# sensors.net
KiCad netlist of a schematic drawn in Altium Designer
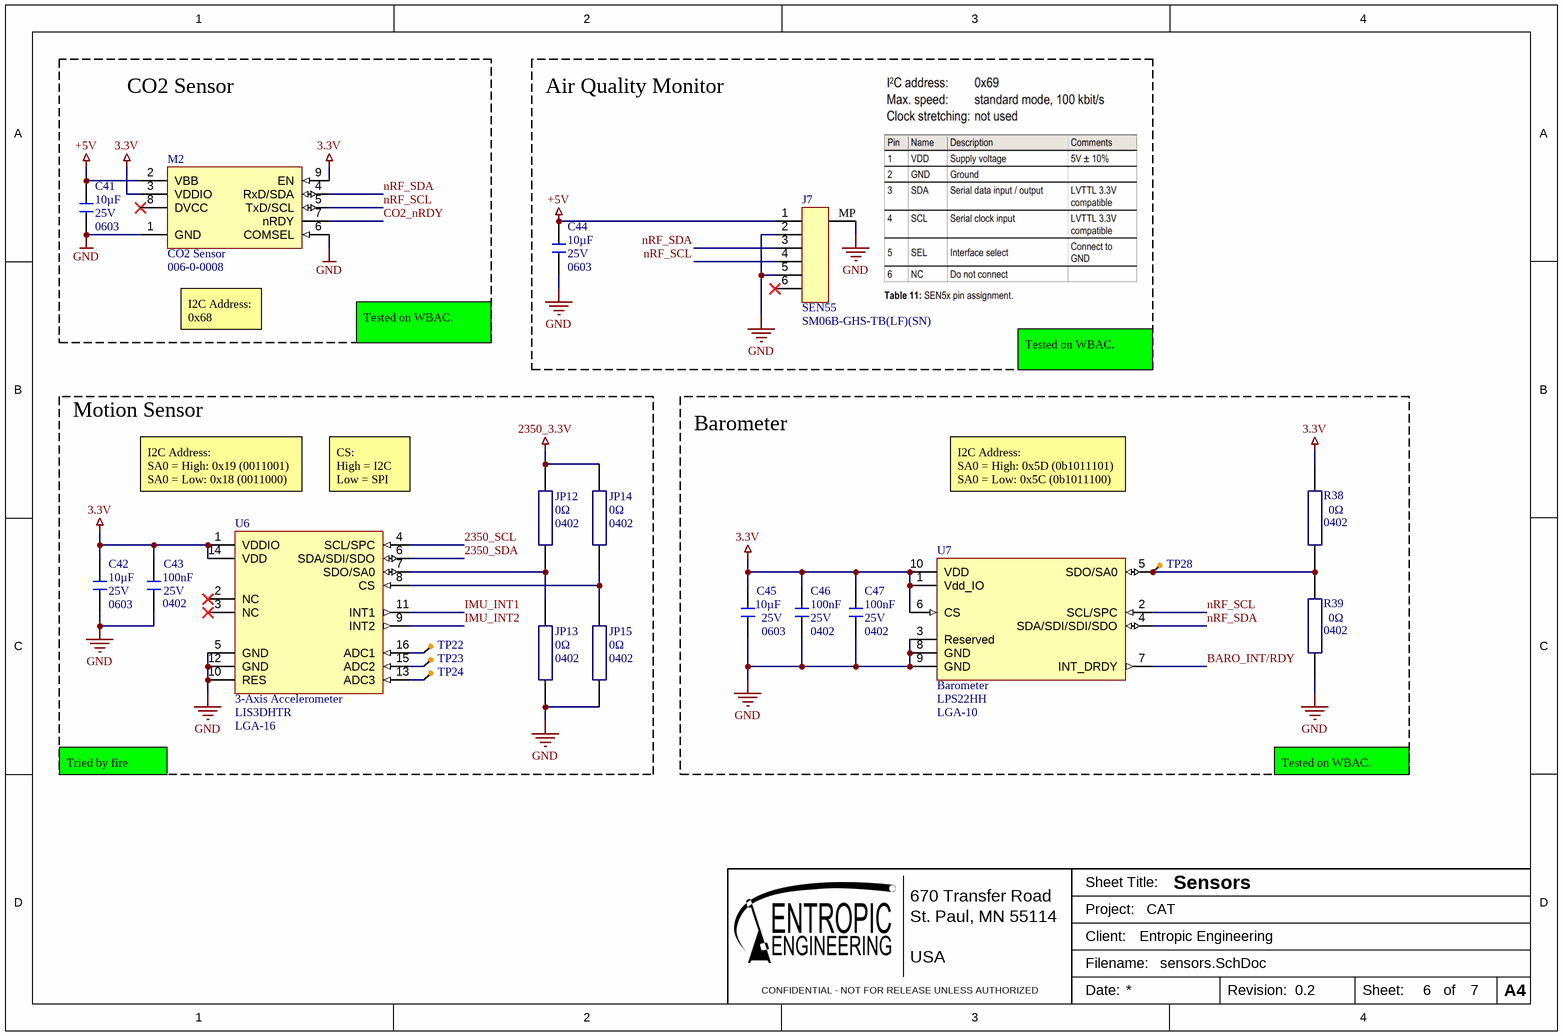
[diagram p0: sensors.SchDoc]

(export (version "E")
  (design (tool "Eeschema 10.0.6"))
  (components
    (comp (ref "C41")
      (value "10µF")
      (footprint "0603_capacitor")
      (description "10 µF, 25 V, X5R, 0603 Chip capacitor")
      (fields
        (field (name "MANUFACTURER") "Samsung")
        (field (name "CASE/PACKAGE") "0603")
        (field (name "TOLERANCE") "20%")
        (field (name "VOLTAGE RATING") "25V")
      )
      (libsource (lib "cat") (part "CL10A106MA8NRNC"))
    )
    (comp (ref "C42")
      (value "10µF")
      (footprint "0603_capacitor")
      (description "10 µF, 25 V, X5R, 0603 Chip capacitor")
      (fields
        (field (name "MANUFACTURER") "Samsung")
        (field (name "CASE/PACKAGE") "0603")
        (field (name "TOLERANCE") "20%")
        (field (name "VOLTAGE RATING") "25V")
      )
      (libsource (lib "cat") (part "CL10A106MA8NRNC"))
    )
    (comp (ref "C43")
      (value "GRM155R71E104KE14D")
      (footprint "0402_capacitor")
      (description "100 nF, 25 V, X7R, 0402 Chip capacitor")
      (fields
        (field (name "MANUFACTURER") "Murata")
        (field (name "TOLERANCE") "10%")
        (field (name "CASE CODE (IMPERIAL)") "0402")
        (field (name "VOLTAGE") "25V")
        (field (name "CAPACITANCE") "100nF")
      )
      (libsource (lib "cat") (part "GRM155R71E104KE14D"))
    )
    (comp (ref "C44")
      (value "10µF")
      (footprint "0603_capacitor")
      (description "10 µF, 25 V, X5R, 0603 Chip capacitor")
      (fields
        (field (name "MANUFACTURER") "Samsung")
        (field (name "CASE/PACKAGE") "0603")
        (field (name "TOLERANCE") "20%")
        (field (name "VOLTAGE RATING") "25V")
      )
      (libsource (lib "cat") (part "CL10A106MA8NRNC"))
    )
    (comp (ref "C45")
      (value "10µF")
      (footprint "0603_capacitor")
      (description "10 µF, 25 V, X5R, 0603 Chip capacitor")
      (fields
        (field (name "MANUFACTURER") "Samsung")
        (field (name "MANUFACTURER PART NUMBER") "CL10A106MA8NRNC")
        (field (name "VOLTAGE RATING") "25V")
        (field (name "CASE/PACKAGE") "0603")
      )
      (libsource (lib "cat") (part "CL10A106MA8NRNC"))
    )
    (comp (ref "C46")
      (value "GRM155R71E104KE14D")
      (footprint "0402_capacitor")
      (description "100 nF, 25 V, X7R, 0402 Chip capacitor")
      (fields
        (field (name "MANUFACTURER") "Murata")
        (field (name "TOLERANCE") "10%")
        (field (name "CASE CODE (IMPERIAL)") "0402")
        (field (name "VOLTAGE") "25V")
        (field (name "CAPACITANCE") "100nF")
      )
      (libsource (lib "cat") (part "GRM155R71E104KE14D"))
    )
    (comp (ref "C47")
      (value "GRM155R71E104KE14D")
      (footprint "0402_capacitor")
      (description "100 nF, 25 V, X7R, 0402 Chip capacitor")
      (fields
        (field (name "MANUFACTURER") "Murata")
        (field (name "TOLERANCE") "10%")
        (field (name "CASE CODE (IMPERIAL)") "0402")
        (field (name "VOLTAGE") "25V")
        (field (name "CAPACITANCE") "100nF")
      )
      (libsource (lib "cat") (part "GRM155R71E104KE14D"))
    )
    (comp (ref "J7")
      (value "SEN55")
      (footprint "SM06B-GHS-TB")
      (description "6-Pin JST GH header, 1.25mm pitch, SMD right angle")
      (fields
        (field (name "MANUFACTURER") "JST")
        (field (name "MANUFACTURER PART NUMBER") "SM06B-GHS-TB(LF)(SN)")
      )
      (libsource (lib "cat") (part "SM06B-GHS-TB(LF)(SN)"))
    )
    (comp (ref "JP12")
      (value "0Ω")
      (footprint "0402_resistor")
      (description "0 Ω, 0402 Chip resistor (jumper)")
      (fields
        (field (name "MANUFACTURER") "Yageo")
        (field (name "MANUFACTURER PART NUMBER") "RC0402FR-070RL")
        (field (name "CASE/PACKAGE") "0402")
      )
      (libsource (lib "cat") (part "RC0402FR-070RL"))
    )
    (comp (ref "JP13")
      (value "0Ω")
      (footprint "0402_resistor")
      (description "0 Ω, 0402 Chip resistor (jumper)")
      (fields
        (field (name "MANUFACTURER") "Yageo")
        (field (name "MANUFACTURER PART NUMBER") "RC0402FR-070RL")
        (field (name "CASE/PACKAGE") "0402")
      )
      (libsource (lib "cat") (part "RC0402FR-070RL"))
    )
    (comp (ref "JP14")
      (value "0Ω")
      (footprint "0402_resistor")
      (description "0 Ω, 0402 Chip resistor (jumper)")
      (fields
        (field (name "MANUFACTURER") "Yageo")
        (field (name "MANUFACTURER PART NUMBER") "RC0402FR-070RL")
        (field (name "CASE/PACKAGE") "0402")
      )
      (libsource (lib "cat") (part "RC0402FR-070RL"))
    )
    (comp (ref "JP15")
      (value "0Ω")
      (footprint "0402_resistor")
      (description "0 Ω, 0402 Chip resistor (jumper)")
      (fields
        (field (name "MANUFACTURER") "Yageo")
        (field (name "MANUFACTURER PART NUMBER") "RC0402FR-070RL")
        (field (name "CASE/PACKAGE") "0402")
      )
      (libsource (lib "cat") (part "RC0402FR-070RL"))
    )
    (comp (ref "M2")
      (value "CO2 Sensor")
      (footprint "006-0-0008")
      (description "Sensair CO2 sensor")
      (fields (field (name "MANUFACTURER PART NUMBER") "006-0-0008"))
      (libsource (lib "cat") (part "006-0-0008"))
    )
    (comp (ref "R38")
      (value "0Ω")
      (footprint "0402_resistor")
      (description "0 Ω, 0402 Chip resistor (jumper)")
      (fields
        (field (name "MANUFACTURER") "Yageo")
        (field (name "MANUFACTURER PART NUMBER") "RC0402FR-070RL")
        (field (name "CASE/PACKAGE") "0402")
      )
      (libsource (lib "cat") (part "RC0402FR-070RL"))
    )
    (comp (ref "R39")
      (value "0Ω")
      (footprint "0402_resistor")
      (description "0 Ω, 0402 Chip resistor (jumper)")
      (fields
        (field (name "MANUFACTURER") "Yageo")
        (field (name "MANUFACTURER PART NUMBER") "RC0402FR-070RL")
        (field (name "CASE/PACKAGE") "0402")
      )
      (libsource (lib "cat") (part "RC0402FR-070RL"))
    )
    (comp (ref "TP22")
      (value "test_point-1")
      (footprint "test_point-1")
      (description "Test point")
      (libsource (lib "cat") (part "test_point-1"))
    )
    (comp (ref "TP23")
      (value "test_point-1")
      (footprint "test_point-1")
      (description "Test point")
      (libsource (lib "cat") (part "test_point-1"))
    )
    (comp (ref "TP24")
      (value "test_point-1")
      (footprint "test_point-1")
      (description "Test point")
      (libsource (lib "cat") (part "test_point-1"))
    )
    (comp (ref "TP28")
      (value "SENSOR_SDA")
      (footprint "test_point-1")
      (description "Test point")
      (libsource (lib "cat") (part "test_point-1"))
    )
    (comp (ref "U6")
      (value "3-Axis Accelerometer")
      (footprint "LGA50P300X300X100-16N")
      (description "3-Axis accelerometer, 16-bit, I2C/SPI, LGA-16")
      (fields
        (field (name "MANUFACTURER") "STMicroelectronics")
        (field (name "CASE/PACKAGE") "LGA-16")
        (field (name "MANUFACTURER PART NUMBER") "LIS3DHTR")
        (field (name "HOUSE_PART_NUMBER") "LIS3DHTR")
      )
      (libsource (lib "cat") (part "LIS3DHTR"))
    )
    (comp (ref "U7")
      (value "Barometer")
      (footprint "LPS22")
      (description "260-1260 hPa Absolute barometer, LGA-10")
      (fields
        (field (name "MANUFACTURER") "STMicroelectronics")
        (field (name "MANUFACTURER PART NUMBER") "LPS22HH")
        (field (name "PACKAGE") "LGA-10")
      )
      (libsource (lib "cat") (part "LPS22HH"))
    )
  )
  (nets
    (net (code "1") (name "+5V") (class "Default")
      (node (ref "C41") (pin "2") (pinfunction "2_2") (pintype "passive"))
      (node (ref "C44") (pin "2") (pinfunction "2_2") (pintype "passive"))
      (node (ref "J7") (pin "1") (pintype "passive"))
      (node (ref "M2") (pin "2") (pinfunction "VBB_2") (pintype "power_in"))
    )
    (net (code "2") (name "/2350_SCL") (class "Default")
      (node (ref "U6") (pin "4") (pinfunction "SCL/SPC_4") (pintype "input"))
    )
    (net (code "3") (name "/2350_SDA") (class "Default")
      (node (ref "U6") (pin "6") (pinfunction "SDA/SDI/SDO_6") (pintype "bidirectional"))
    )
    (net (code "4") (name "/BARO_INT{slash}RDY") (class "Default")
      (node (ref "U7") (pin "7") (pinfunction "INT_DRDY_7") (pintype "output"))
    )
    (net (code "5") (name "/CO2_nRDY") (class "Default")
      (node (ref "M2") (pin "7") (pinfunction "nRDY_7") (pintype "open_collector"))
    )
    (net (code "6") (name "/IMU_INT1") (class "Default")
      (node (ref "U6") (pin "11") (pinfunction "INT1_11") (pintype "output"))
    )
    (net (code "7") (name "/IMU_INT2") (class "Default")
      (node (ref "U6") (pin "9") (pinfunction "INT2_9") (pintype "output"))
    )
    (net (code "8") (name "/nRF_SCL") (class "Default")
      (node (ref "J7") (pin "4") (pintype "passive"))
      (node (ref "M2") (pin "5") (pinfunction "TxD/SCL_5") (pintype "bidirectional"))
      (node (ref "U7") (pin "2") (pinfunction "SCL/SPC_2") (pintype "input"))
    )
    (net (code "9") (name "/nRF_SDA") (class "Default")
      (node (ref "J7") (pin "3") (pintype "passive"))
      (node (ref "M2") (pin "4") (pinfunction "RxD/SDA_4") (pintype "bidirectional"))
      (node (ref "U7") (pin "4") (pinfunction "SDA/SDI/SDI/SDO_4") (pintype "bidirectional"))
    )
    (net (code "10") (name "3.3V") (class "Default")
      (node (ref "C42") (pin "2") (pinfunction "2_2") (pintype "passive"))
      (node (ref "C43") (pin "2") (pinfunction "2_2") (pintype "passive"))
      (node (ref "C45") (pin "2") (pinfunction "2_2") (pintype "passive"))
      (node (ref "C46") (pin "2") (pinfunction "2_2") (pintype "passive"))
      (node (ref "C47") (pin "2") (pinfunction "2_2") (pintype "passive"))
      (node (ref "M2") (pin "3") (pinfunction "VDDIO_3") (pintype "power_in"))
      (node (ref "M2") (pin "9") (pinfunction "EN_9") (pintype "input"))
      (node (ref "R38") (pin "1") (pinfunction "1_1") (pintype "passive"))
      (node (ref "U6") (pin "1") (pinfunction "VDDIO_1") (pintype "power_in"))
      (node (ref "U6") (pin "14") (pinfunction "VDD_14") (pintype "power_in"))
      (node (ref "U7") (pin "1") (pinfunction "Vdd_IO_1") (pintype "power_in"))
      (node (ref "U7") (pin "10") (pinfunction "VDD_10") (pintype "power_in"))
      (node (ref "U7") (pin "6") (pinfunction "CS_6") (pintype "input"))
    )
    (net (code "11") (name "2350_3.3V") (class "Default")
      (node (ref "JP12") (pin "1") (pinfunction "1_1") (pintype "passive"))
      (node (ref "JP14") (pin "1") (pinfunction "1_1") (pintype "passive"))
    )
    (net (code "12") (name "GND") (class "Default")
      (node (ref "C41") (pin "1") (pinfunction "1_1") (pintype "passive"))
      (node (ref "C42") (pin "1") (pinfunction "1_1") (pintype "passive"))
      (node (ref "C43") (pin "1") (pinfunction "1_1") (pintype "passive"))
      (node (ref "C44") (pin "1") (pinfunction "1_1") (pintype "passive"))
      (node (ref "C45") (pin "1") (pinfunction "1_1") (pintype "passive"))
      (node (ref "C46") (pin "1") (pinfunction "1_1") (pintype "passive"))
      (node (ref "C47") (pin "1") (pinfunction "1_1") (pintype "passive"))
      (node (ref "J7") (pin "2") (pintype "passive"))
      (node (ref "J7") (pin "5") (pintype "passive"))
      (node (ref "J7") (pin "MP") (pintype "passive"))
      (node (ref "JP13") (pin "2") (pinfunction "2_2") (pintype "passive"))
      (node (ref "JP15") (pin "2") (pinfunction "2_2") (pintype "passive"))
      (node (ref "M2") (pin "1") (pinfunction "GND_1") (pintype "power_in"))
      (node (ref "M2") (pin "6") (pinfunction "COMSEL_6") (pintype "input"))
      (node (ref "R39") (pin "2") (pinfunction "2_2") (pintype "passive"))
      (node (ref "U6") (pin "10") (pinfunction "RES_10") (pintype "power_in"))
      (node (ref "U6") (pin "12") (pinfunction "GND_12") (pintype "power_in"))
      (node (ref "U6") (pin "5") (pinfunction "GND_5") (pintype "power_in"))
      (node (ref "U7") (pin "3") (pinfunction "Reserved_3") (pintype "power_in"))
      (node (ref "U7") (pin "8") (pinfunction "GND_8") (pintype "power_in"))
      (node (ref "U7") (pin "9") (pinfunction "GND_9") (pintype "power_in"))
    )
    (net (code "13") (name "Net-(U6-ADC1)") (class "Default")
      (node (ref "TP22") (pin "1") (pinfunction "1_1") (pintype "passive"))
      (node (ref "U6") (pin "16") (pinfunction "ADC1_16") (pintype "input"))
    )
    (net (code "14") (name "Net-(U6-ADC2)") (class "Default")
      (node (ref "TP23") (pin "1") (pinfunction "1_1") (pintype "passive"))
      (node (ref "U6") (pin "15") (pinfunction "ADC2_15") (pintype "input"))
    )
    (net (code "15") (name "Net-(U6-ADC3)") (class "Default")
      (node (ref "TP24") (pin "1") (pinfunction "1_1") (pintype "passive"))
      (node (ref "U6") (pin "13") (pinfunction "ADC3_13") (pintype "input"))
    )
    (net (code "16") (name "Net-(U6-CS)") (class "Default")
      (node (ref "JP14") (pin "2") (pinfunction "2_2") (pintype "passive"))
      (node (ref "JP15") (pin "1") (pinfunction "1_1") (pintype "passive"))
      (node (ref "U6") (pin "8") (pinfunction "CS_8") (pintype "input"))
    )
    (net (code "17") (name "Net-(U6-SDO{slash}SA0)") (class "Default")
      (node (ref "JP12") (pin "2") (pinfunction "2_2") (pintype "passive"))
      (node (ref "JP13") (pin "1") (pinfunction "1_1") (pintype "passive"))
      (node (ref "U6") (pin "7") (pinfunction "SDO/SA0_7") (pintype "bidirectional"))
    )
    (net (code "18") (name "Net-(U7-SDO{slash}SA0)") (class "Default")
      (node (ref "R38") (pin "2") (pinfunction "2_2") (pintype "passive"))
      (node (ref "R39") (pin "1") (pinfunction "1_1") (pintype "passive"))
      (node (ref "TP28") (pin "1") (pinfunction "1_1") (pintype "passive"))
      (node (ref "U7") (pin "5") (pinfunction "SDO/SA0_5") (pintype "bidirectional"))
    )
    (net (code "19") (name "unconnected-(J7-Pad6)") (class "Default")
      (node (ref "J7") (pin "6") (pintype "passive+no_connect"))
    )
    (net (code "20") (name "unconnected-(M2-DVCC-Pad8)") (class "Default")
      (node (ref "M2") (pin "8") (pinfunction "DVCC_8") (pintype "power_in+no_connect"))
    )
    (net (code "21") (name "unconnected-(U6-NC-Pad2)") (class "Default")
      (node (ref "U6") (pin "2") (pinfunction "NC_2") (pintype "power_in+no_connect"))
    )
    (net (code "22") (name "unconnected-(U6-NC-Pad3)") (class "Default")
      (node (ref "U6") (pin "3") (pinfunction "NC_3") (pintype "power_in+no_connect"))
    )
  )
)
